# SparkFun_LilyPad_Buzzer.net
KiCad netlist of a schematic drawn in EAGLE
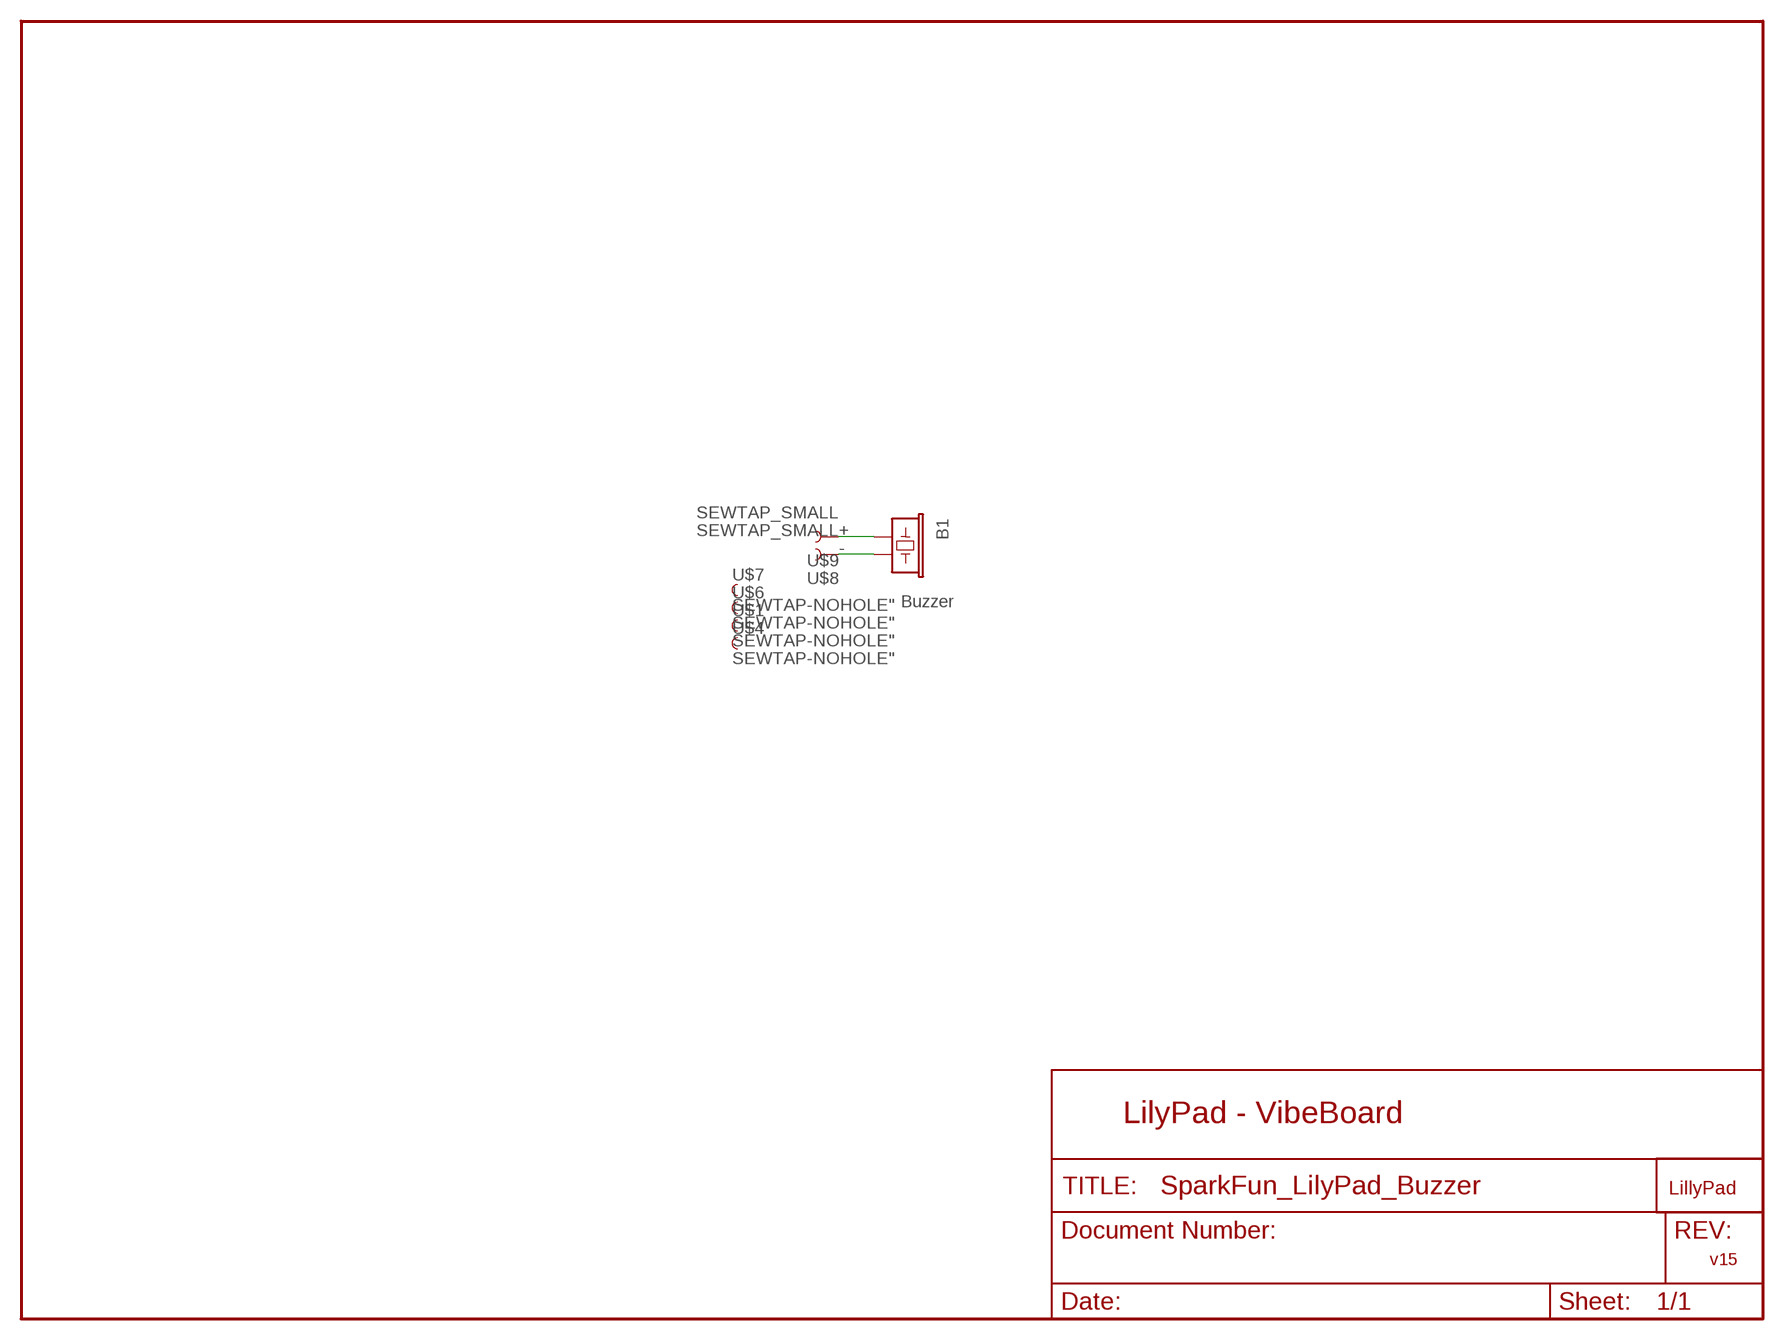
[diagram p0: schematic, sheet 1]

(export (version "E")
  (design (tool "Eeschema 10.0.6"))
  (components
    (comp (ref "B1")
      (value "Buzzer")
      (footprint "eagle-import:BUZZER-CCV")
      (libsource (lib "eagle-import") (part "BUZZERSMD2"))
    )
    (comp (ref "U$1")
      (value "SEWTAP-NOHOLE\"")
      (footprint "eagle-import:PETAL-NOHOLE")
      (libsource (lib "eagle-import") (part "SEWTAP-NOHOLE{dblquote}"))
    )
    (comp (ref "U$2")
      (value "LOGO-LPLP")
      (footprint "eagle-import:LOGO-LILYPAD")
      (libsource (lib "eagle-import") (part "LOGO-LPLP"))
    )
    (comp (ref "U$4")
      (value "SEWTAP-NOHOLE\"")
      (footprint "eagle-import:PETAL-NOHOLE")
      (libsource (lib "eagle-import") (part "SEWTAP-NOHOLE{dblquote}"))
    )
    (comp (ref "U$6")
      (value "SEWTAP-NOHOLE\"")
      (footprint "eagle-import:PETAL-NOHOLE")
      (libsource (lib "eagle-import") (part "SEWTAP-NOHOLE{dblquote}"))
    )
    (comp (ref "U$7")
      (value "SEWTAP-NOHOLE\"")
      (footprint "eagle-import:PETAL-NOHOLE")
      (libsource (lib "eagle-import") (part "SEWTAP-NOHOLE{dblquote}"))
    )
    (comp (ref "U$8")
      (value "SEWTAP_SMALL")
      (footprint "eagle-import:PETAL-SMALL")
      (libsource (lib "eagle-import") (part "SEWTAP_SMALL"))
    )
    (comp (ref "U$9")
      (value "SEWTAP_SMALL")
      (footprint "eagle-import:PETAL-SMALL")
      (libsource (lib "eagle-import") (part "SEWTAP_SMALL"))
    )
  )
  (nets
    (net (code "1") (name "/+") (class "Default")
      (node (ref "B1") (pin "+") (pinfunction "1_+") (pintype "passive"))
      (node (ref "U$9") (pin "1") (pinfunction "1_1") (pintype "bidirectional"))
    )
    (net (code "2") (name "/-") (class "Default")
      (node (ref "B1") (pin "-") (pinfunction "2_-") (pintype "passive"))
      (node (ref "U$8") (pin "1") (pinfunction "1_1") (pintype "bidirectional"))
    )
  )
)
